# Connectors.net
KiCad netlist of a schematic drawn in Altium Designer
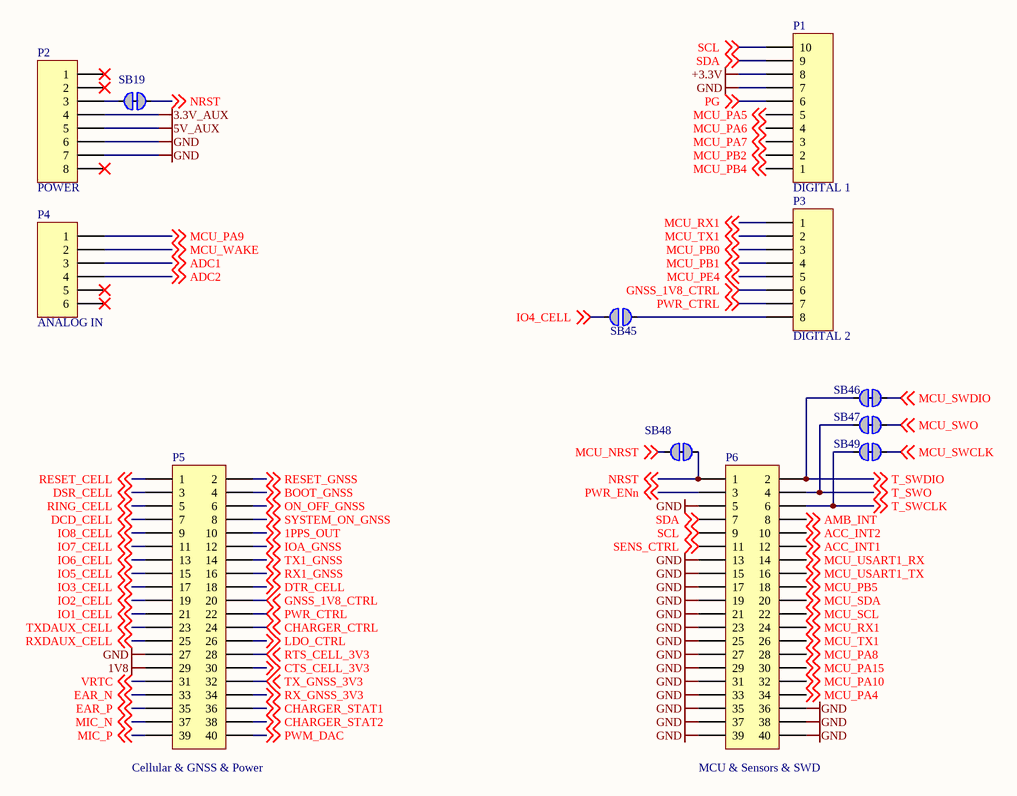
[diagram p0: Connectors.SchDoc]

(export (version "E")
  (design (tool "Eeschema 10.0.6"))
  (components
    (comp (ref "P1")
      (value "DIGITAL 1")
      (footprint "HDR1X10")
      (fields
        (field (name "MANUFACTURER") "SparkFun Electronics")
        (field (name "MANUFACTURER PART NO.") "PRT-11417")
      )
      (libsource (lib "Miscellaneous Connectors") (part "Header 10"))
    )
    (comp (ref "P2")
      (value "POWER")
      (footprint "HDR1X8")
      (libsource (lib "Miscellaneous Connectors") (part "Header 8"))
    )
    (comp (ref "P3") (value "DIGITAL 2") (footprint "HDR1X8") (libsource (lib "") (part "Header 8_1")))
    (comp (ref "P4")
      (value "ANALOG IN")
      (footprint "HDR1X6")
      (libsource (lib "Miscellaneous Connectors") (part "Header 6"))
    )
    (comp (ref "P5")
      (value "Cellular & GNSS & Power")
      (footprint "HDR2X20")
      (fields
        (field (name "MANUFACTURER") "MPE-Garry")
        (field (name "MANUFACTURER PART NO.") "087-2-040-0-S-XS0-1260")
      )
      (libsource (lib "Miscellaneous Connectors") (part "Header 20X2"))
    )
    (comp (ref "P6")
      (value "MCU & Sensors & SWD")
      (footprint "HDR2X20")
      (fields
        (field (name "MANUFACTURER") "MPE-Garry")
        (field (name "MANUFACTURER PART NO.") "087-2-040-0-S-XS0-1260")
      )
      (libsource (lib "Miscellaneous Connectors") (part "Header 20X2"))
    )
    (comp (ref "SB19")
      (value "Solderbridge")
      (footprint "Solderbridge_Shorted")
      (libsource (lib "altium-import") (part "root_0_SOLDERBRIDGE_SHORTED_"))
    )
    (comp (ref "SB45")
      (value "Solderbridge")
      (footprint "Solderbridge")
      (libsource (lib "altium-import") (part "root_0_SOLDERBRIDGE_"))
    )
    (comp (ref "SB46")
      (value "Solderbridge")
      (footprint "Solderbridge_Shorted")
      (libsource (lib "altium-import") (part "root_2_SOLDERBRIDGE_SHORTED_"))
    )
    (comp (ref "SB47")
      (value "Solderbridge")
      (footprint "Solderbridge_Shorted")
      (libsource (lib "altium-import") (part "root_2_SOLDERBRIDGE_SHORTED_"))
    )
    (comp (ref "SB48")
      (value "Solderbridge")
      (footprint "Solderbridge_Shorted")
      (libsource (lib "altium-import") (part "root_2_SOLDERBRIDGE_SHORTED_"))
    )
    (comp (ref "SB49")
      (value "Solderbridge")
      (footprint "Solderbridge_Shorted")
      (libsource (lib "altium-import") (part "root_2_SOLDERBRIDGE_SHORTED_"))
    )
  )
  (nets
    (net (code "1") (name "+3.3V") (class "Default")
      (node (ref "P1") (pin "8") (pinfunction "8_8") (pintype "passive"))
    )
    (net (code "2") (name "1PPS_OUT") (class "Default")
      (node (ref "P5") (pin "10") (pinfunction "10_10") (pintype "passive"))
    )
    (net (code "3") (name "1V8") (class "Default")
      (node (ref "P5") (pin "29") (pinfunction "29_29") (pintype "passive"))
    )
    (net (code "4") (name "3.3V_AUX") (class "Default")
      (node (ref "P2") (pin "4") (pinfunction "4_4") (pintype "passive"))
    )
    (net (code "5") (name "5V_AUX") (class "Default")
      (node (ref "P2") (pin "5") (pinfunction "5_5") (pintype "passive"))
    )
    (net (code "6") (name "ACC_INT1") (class "Default")
      (node (ref "P6") (pin "12") (pinfunction "12_12") (pintype "passive"))
    )
    (net (code "7") (name "ACC_INT2") (class "Default")
      (node (ref "P6") (pin "10") (pinfunction "10_10") (pintype "passive"))
    )
    (net (code "8") (name "ADC1") (class "Default")
      (node (ref "P4") (pin "3") (pinfunction "3_3") (pintype "passive"))
    )
    (net (code "9") (name "ADC2") (class "Default")
      (node (ref "P4") (pin "4") (pinfunction "4_4") (pintype "passive"))
    )
    (net (code "10") (name "AMB_INT") (class "Default")
      (node (ref "P6") (pin "8") (pinfunction "8_8") (pintype "passive"))
    )
    (net (code "11") (name "BOOT_GNSS") (class "Default")
      (node (ref "P5") (pin "4") (pinfunction "4_4") (pintype "passive"))
    )
    (net (code "12") (name "CHARGER_CTRL") (class "Default")
      (node (ref "P5") (pin "24") (pinfunction "24_24") (pintype "passive"))
    )
    (net (code "13") (name "CHARGER_STAT1") (class "Default")
      (node (ref "P5") (pin "36") (pinfunction "36_36") (pintype "passive"))
    )
    (net (code "14") (name "CHARGER_STAT2") (class "Default")
      (node (ref "P5") (pin "38") (pinfunction "38_38") (pintype "passive"))
    )
    (net (code "15") (name "CTS_CELL_3V3") (class "Default")
      (node (ref "P5") (pin "30") (pinfunction "30_30") (pintype "passive"))
    )
    (net (code "16") (name "DCD_CELL") (class "Default")
      (node (ref "P5") (pin "7") (pinfunction "7_7") (pintype "passive"))
    )
    (net (code "17") (name "DSR_CELL") (class "Default")
      (node (ref "P5") (pin "3") (pinfunction "3_3") (pintype "passive"))
    )
    (net (code "18") (name "DTR_CELL") (class "Default")
      (node (ref "P5") (pin "18") (pinfunction "18_18") (pintype "passive"))
    )
    (net (code "19") (name "EAR_N") (class "Default")
      (node (ref "P5") (pin "33") (pinfunction "33_33") (pintype "passive"))
    )
    (net (code "20") (name "EAR_P") (class "Default")
      (node (ref "P5") (pin "35") (pinfunction "35_35") (pintype "passive"))
    )
    (net (code "21") (name "GND") (class "Default")
      (node (ref "P1") (pin "7") (pinfunction "7_7") (pintype "passive"))
      (node (ref "P2") (pin "6") (pinfunction "6_6") (pintype "passive"))
      (node (ref "P2") (pin "7") (pinfunction "7_7") (pintype "passive"))
      (node (ref "P5") (pin "27") (pinfunction "27_27") (pintype "passive"))
      (node (ref "P6") (pin "13") (pinfunction "13_13") (pintype "passive"))
      (node (ref "P6") (pin "15") (pinfunction "15_15") (pintype "passive"))
      (node (ref "P6") (pin "17") (pinfunction "17_17") (pintype "passive"))
      (node (ref "P6") (pin "19") (pinfunction "19_19") (pintype "passive"))
      (node (ref "P6") (pin "21") (pinfunction "21_21") (pintype "passive"))
      (node (ref "P6") (pin "23") (pinfunction "23_23") (pintype "passive"))
      (node (ref "P6") (pin "25") (pinfunction "25_25") (pintype "passive"))
      (node (ref "P6") (pin "27") (pinfunction "27_27") (pintype "passive"))
      (node (ref "P6") (pin "29") (pinfunction "29_29") (pintype "passive"))
      (node (ref "P6") (pin "31") (pinfunction "31_31") (pintype "passive"))
      (node (ref "P6") (pin "33") (pinfunction "33_33") (pintype "passive"))
      (node (ref "P6") (pin "35") (pinfunction "35_35") (pintype "passive"))
      (node (ref "P6") (pin "36") (pinfunction "36_36") (pintype "passive"))
      (node (ref "P6") (pin "37") (pinfunction "37_37") (pintype "passive"))
      (node (ref "P6") (pin "38") (pinfunction "38_38") (pintype "passive"))
      (node (ref "P6") (pin "39") (pinfunction "39_39") (pintype "passive"))
      (node (ref "P6") (pin "40") (pinfunction "40_40") (pintype "passive"))
      (node (ref "P6") (pin "5") (pinfunction "5_5") (pintype "passive"))
    )
    (net (code "22") (name "GNSS_1V8_CTRL") (class "Default")
      (node (ref "P3") (pin "6") (pinfunction "6_6") (pintype "passive"))
      (node (ref "P5") (pin "20") (pinfunction "20_20") (pintype "passive"))
    )
    (net (code "23") (name "IO1_CELL") (class "Default")
      (node (ref "P5") (pin "21") (pinfunction "21_21") (pintype "passive"))
    )
    (net (code "24") (name "IO2_CELL") (class "Default")
      (node (ref "P5") (pin "19") (pinfunction "19_19") (pintype "passive"))
    )
    (net (code "25") (name "IO3_CELL") (class "Default")
      (node (ref "P5") (pin "17") (pinfunction "17_17") (pintype "passive"))
    )
    (net (code "26") (name "IO4_CELL") (class "Default")
      (node (ref "SB45") (pin "2") (pinfunction "1_2") (pintype "passive"))
    )
    (net (code "27") (name "IO5_CELL") (class "Default")
      (node (ref "P5") (pin "15") (pinfunction "15_15") (pintype "passive"))
    )
    (net (code "28") (name "IO6_CELL") (class "Default")
      (node (ref "P5") (pin "13") (pinfunction "13_13") (pintype "passive"))
    )
    (net (code "29") (name "IO7_CELL") (class "Default")
      (node (ref "P5") (pin "11") (pinfunction "11_11") (pintype "passive"))
    )
    (net (code "30") (name "IO8_CELL") (class "Default")
      (node (ref "P5") (pin "9") (pinfunction "9_9") (pintype "passive"))
    )
    (net (code "31") (name "IOA_GNSS") (class "Default")
      (node (ref "P5") (pin "12") (pinfunction "12_12") (pintype "passive"))
    )
    (net (code "32") (name "LDO_CTRL") (class "Default")
      (node (ref "P5") (pin "26") (pinfunction "26_26") (pintype "passive"))
    )
    (net (code "33") (name "MCU_NRST") (class "Default")
      (node (ref "SB48") (pin "1") (pinfunction "0_1") (pintype "passive"))
    )
    (net (code "34") (name "MCU_PA4") (class "Default")
      (node (ref "P6") (pin "34") (pinfunction "34_34") (pintype "passive"))
    )
    (net (code "35") (name "MCU_PA5") (class "Default")
      (node (ref "P1") (pin "5") (pinfunction "5_5") (pintype "passive"))
    )
    (net (code "36") (name "MCU_PA6") (class "Default")
      (node (ref "P1") (pin "4") (pinfunction "4_4") (pintype "passive"))
    )
    (net (code "37") (name "MCU_PA7") (class "Default")
      (node (ref "P1") (pin "3") (pinfunction "3_3") (pintype "passive"))
    )
    (net (code "38") (name "MCU_PA8") (class "Default")
      (node (ref "P6") (pin "28") (pinfunction "28_28") (pintype "passive"))
    )
    (net (code "39") (name "MCU_PA9") (class "Default")
      (node (ref "P4") (pin "1") (pinfunction "1_1") (pintype "passive"))
    )
    (net (code "40") (name "MCU_PA10") (class "Default")
      (node (ref "P6") (pin "32") (pinfunction "32_32") (pintype "passive"))
    )
    (net (code "41") (name "MCU_PA15") (class "Default")
      (node (ref "P6") (pin "30") (pinfunction "30_30") (pintype "passive"))
    )
    (net (code "42") (name "MCU_PB0") (class "Default")
      (node (ref "P3") (pin "3") (pinfunction "3_3") (pintype "passive"))
    )
    (net (code "43") (name "MCU_PB1") (class "Default")
      (node (ref "P3") (pin "4") (pinfunction "4_4") (pintype "passive"))
    )
    (net (code "44") (name "MCU_PB2") (class "Default")
      (node (ref "P1") (pin "2") (pinfunction "2_2") (pintype "passive"))
    )
    (net (code "45") (name "MCU_PB4") (class "Default")
      (node (ref "P1") (pin "1") (pinfunction "1_1") (pintype "passive"))
    )
    (net (code "46") (name "MCU_PB5") (class "Default")
      (node (ref "P6") (pin "18") (pinfunction "18_18") (pintype "passive"))
    )
    (net (code "47") (name "MCU_PE4") (class "Default")
      (node (ref "P3") (pin "5") (pinfunction "5_5") (pintype "passive"))
    )
    (net (code "48") (name "MCU_RX1") (class "Default")
      (node (ref "P3") (pin "1") (pinfunction "1_1") (pintype "passive"))
      (node (ref "P6") (pin "24") (pinfunction "24_24") (pintype "passive"))
    )
    (net (code "49") (name "MCU_SCL") (class "Default")
      (node (ref "P6") (pin "22") (pinfunction "22_22") (pintype "passive"))
    )
    (net (code "50") (name "MCU_SDA") (class "Default")
      (node (ref "P6") (pin "20") (pinfunction "20_20") (pintype "passive"))
    )
    (net (code "51") (name "MCU_SWCLK") (class "Default")
      (node (ref "SB49") (pin "2") (pinfunction "1_2") (pintype "passive"))
    )
    (net (code "52") (name "MCU_SWDIO") (class "Default")
      (node (ref "SB46") (pin "2") (pinfunction "1_2") (pintype "passive"))
    )
    (net (code "53") (name "MCU_SWO") (class "Default")
      (node (ref "SB47") (pin "2") (pinfunction "1_2") (pintype "passive"))
    )
    (net (code "54") (name "MCU_TX1") (class "Default")
      (node (ref "P3") (pin "2") (pinfunction "2_2") (pintype "passive"))
      (node (ref "P6") (pin "26") (pinfunction "26_26") (pintype "passive"))
    )
    (net (code "55") (name "MCU_USART1_RX") (class "Default")
      (node (ref "P6") (pin "14") (pinfunction "14_14") (pintype "passive"))
    )
    (net (code "56") (name "MCU_USART1_TX") (class "Default")
      (node (ref "P6") (pin "16") (pinfunction "16_16") (pintype "passive"))
    )
    (net (code "57") (name "MCU_WAKE") (class "Default")
      (node (ref "P4") (pin "2") (pinfunction "2_2") (pintype "passive"))
    )
    (net (code "58") (name "MIC_N") (class "Default")
      (node (ref "P5") (pin "37") (pinfunction "37_37") (pintype "passive"))
    )
    (net (code "59") (name "MIC_P") (class "Default")
      (node (ref "P5") (pin "39") (pinfunction "39_39") (pintype "passive"))
    )
    (net (code "60") (name "NRST") (class "Default")
      (node (ref "P6") (pin "1") (pinfunction "1_1") (pintype "passive"))
      (node (ref "SB19") (pin "1") (pinfunction "0_1") (pintype "passive"))
      (node (ref "SB48") (pin "2") (pinfunction "1_2") (pintype "passive"))
    )
    (net (code "61") (name "Net-(SB19-1)") (class "Default")
      (node (ref "P2") (pin "3") (pinfunction "3_3") (pintype "passive"))
      (node (ref "SB19") (pin "2") (pinfunction "1_2") (pintype "passive"))
    )
    (net (code "62") (name "Net-(SB45-0)") (class "Default")
      (node (ref "P3") (pin "8") (pinfunction "8_8") (pintype "passive"))
      (node (ref "SB45") (pin "1") (pinfunction "0_1") (pintype "passive"))
    )
    (net (code "63") (name "ON_OFF_GNSS") (class "Default")
      (node (ref "P5") (pin "6") (pinfunction "6_6") (pintype "passive"))
    )
    (net (code "64") (name "PG") (class "Default")
      (node (ref "P1") (pin "6") (pinfunction "6_6") (pintype "passive"))
    )
    (net (code "65") (name "PWM_DAC") (class "Default")
      (node (ref "P5") (pin "40") (pinfunction "40_40") (pintype "passive"))
    )
    (net (code "66") (name "PWR_CTRL") (class "Default")
      (node (ref "P3") (pin "7") (pinfunction "7_7") (pintype "passive"))
      (node (ref "P5") (pin "22") (pinfunction "22_22") (pintype "passive"))
    )
    (net (code "67") (name "PWR_ENn") (class "Default")
      (node (ref "P6") (pin "3") (pinfunction "3_3") (pintype "passive"))
    )
    (net (code "68") (name "RESET_CELL") (class "Default")
      (node (ref "P5") (pin "1") (pinfunction "1_1") (pintype "passive"))
    )
    (net (code "69") (name "RESET_GNSS") (class "Default")
      (node (ref "P5") (pin "2") (pinfunction "2_2") (pintype "passive"))
    )
    (net (code "70") (name "RING_CELL") (class "Default")
      (node (ref "P5") (pin "5") (pinfunction "5_5") (pintype "passive"))
    )
    (net (code "71") (name "RTS_CELL_3V3") (class "Default")
      (node (ref "P5") (pin "28") (pinfunction "28_28") (pintype "passive"))
    )
    (net (code "72") (name "RX1_GNSS") (class "Default")
      (node (ref "P5") (pin "16") (pinfunction "16_16") (pintype "passive"))
    )
    (net (code "73") (name "RXDAUX_CELL") (class "Default")
      (node (ref "P5") (pin "25") (pinfunction "25_25") (pintype "passive"))
    )
    (net (code "74") (name "RX_GNSS_3V3") (class "Default")
      (node (ref "P5") (pin "34") (pinfunction "34_34") (pintype "passive"))
    )
    (net (code "75") (name "SCL") (class "Default")
      (node (ref "P1") (pin "10") (pinfunction "10_10") (pintype "passive"))
      (node (ref "P6") (pin "9") (pinfunction "9_9") (pintype "passive"))
    )
    (net (code "76") (name "SDA") (class "Default")
      (node (ref "P1") (pin "9") (pinfunction "9_9") (pintype "passive"))
      (node (ref "P6") (pin "7") (pinfunction "7_7") (pintype "passive"))
    )
    (net (code "77") (name "SENS_CTRL") (class "Default")
      (node (ref "P6") (pin "11") (pinfunction "11_11") (pintype "passive"))
    )
    (net (code "78") (name "SYSTEM_ON_GNSS") (class "Default")
      (node (ref "P5") (pin "8") (pinfunction "8_8") (pintype "passive"))
    )
    (net (code "79") (name "TX1_GNSS") (class "Default")
      (node (ref "P5") (pin "14") (pinfunction "14_14") (pintype "passive"))
    )
    (net (code "80") (name "TXDAUX_CELL") (class "Default")
      (node (ref "P5") (pin "23") (pinfunction "23_23") (pintype "passive"))
    )
    (net (code "81") (name "TX_GNSS_3V3") (class "Default")
      (node (ref "P5") (pin "32") (pinfunction "32_32") (pintype "passive"))
    )
    (net (code "82") (name "T_SWCLK") (class "Default")
      (node (ref "P6") (pin "6") (pinfunction "6_6") (pintype "passive"))
      (node (ref "SB49") (pin "1") (pinfunction "0_1") (pintype "passive"))
    )
    (net (code "83") (name "T_SWDIO") (class "Default")
      (node (ref "P6") (pin "2") (pinfunction "2_2") (pintype "passive"))
      (node (ref "SB46") (pin "1") (pinfunction "0_1") (pintype "passive"))
    )
    (net (code "84") (name "T_SWO") (class "Default")
      (node (ref "P6") (pin "4") (pinfunction "4_4") (pintype "passive"))
      (node (ref "SB47") (pin "1") (pinfunction "0_1") (pintype "passive"))
    )
    (net (code "85") (name "VRTC") (class "Default")
      (node (ref "P5") (pin "31") (pinfunction "31_31") (pintype "passive"))
    )
    (net (code "86") (name "unconnected-(P2-Pad1)") (class "Default")
      (node (ref "P2") (pin "1") (pinfunction "1_1") (pintype "passive+no_connect"))
    )
    (net (code "87") (name "unconnected-(P2-Pad2)") (class "Default")
      (node (ref "P2") (pin "2") (pinfunction "2_2") (pintype "passive+no_connect"))
    )
    (net (code "88") (name "unconnected-(P2-Pad8)") (class "Default")
      (node (ref "P2") (pin "8") (pinfunction "8_8") (pintype "passive+no_connect"))
    )
    (net (code "89") (name "unconnected-(P4-Pad5)") (class "Default")
      (node (ref "P4") (pin "5") (pinfunction "5_5") (pintype "passive+no_connect"))
    )
    (net (code "90") (name "unconnected-(P4-Pad6)") (class "Default")
      (node (ref "P4") (pin "6") (pinfunction "6_6") (pintype "passive+no_connect"))
    )
  )
)
